# FPGA.net
KiCad netlist of a schematic drawn in Altium Designer
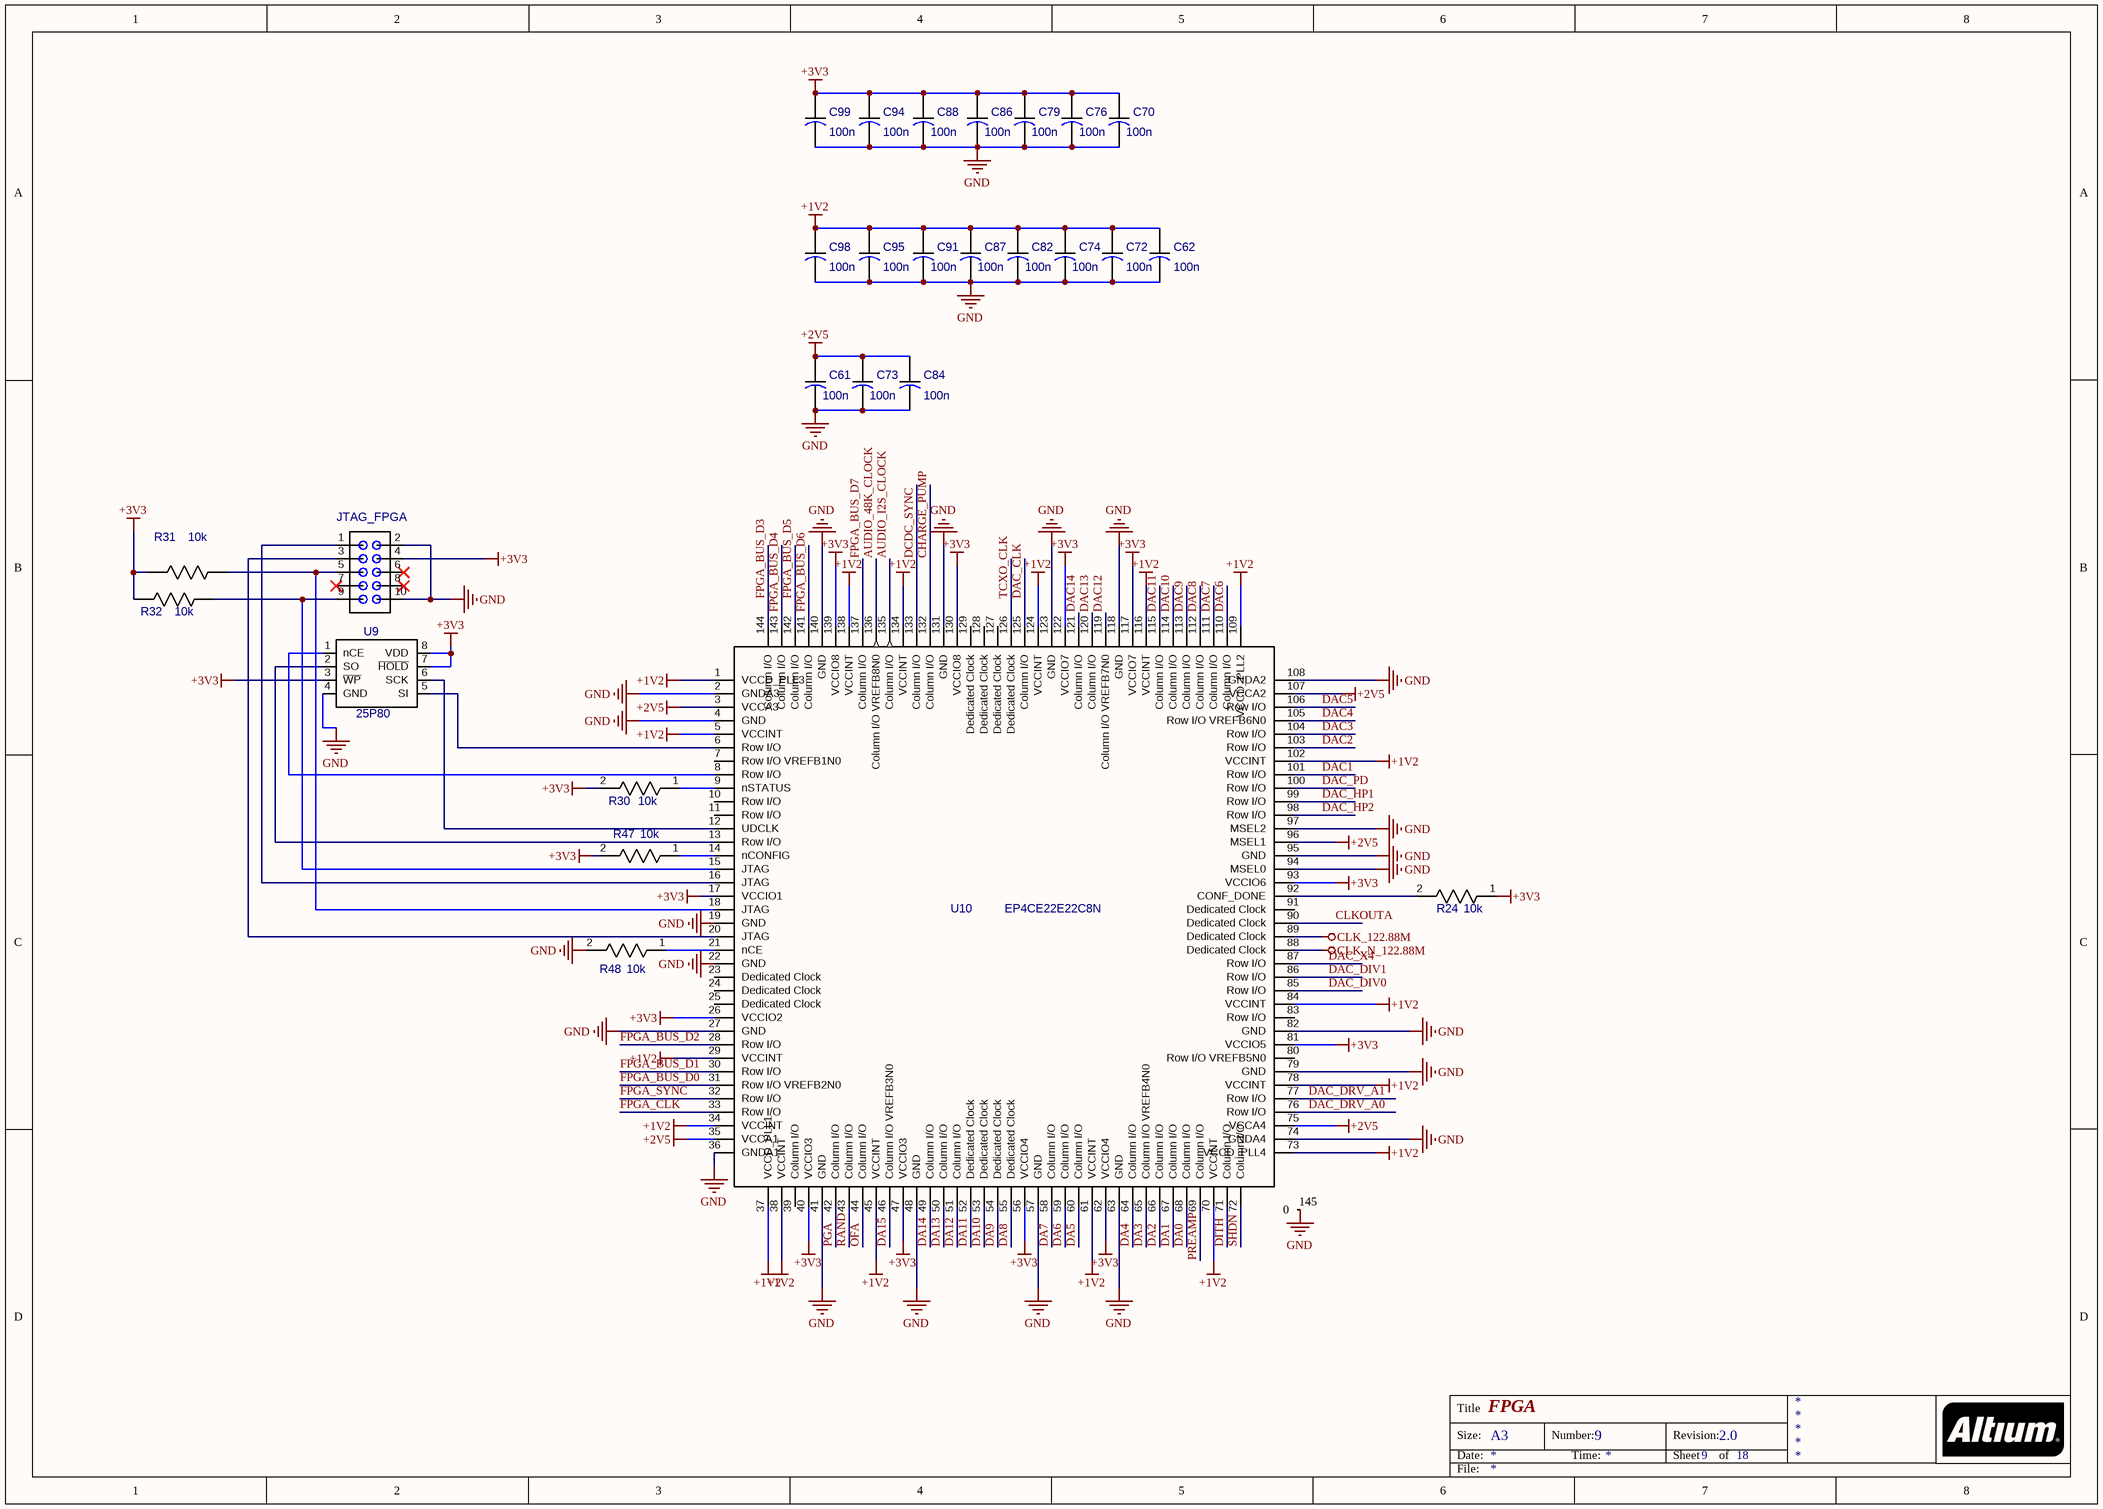
[diagram p0: FPGA.SchDoc]

(export (version "E")
  (design (tool "Eeschema 10.0.6"))
  (components
    (comp (ref "C61")
      (value "100n")
      (footprint "CAP_0805")
      (description "CAP_0805")
      (libsource (lib "*") (part "CAP_0805"))
    )
    (comp (ref "C62")
      (value "100n")
      (footprint "CAP_0805")
      (description "CAP_0805")
      (libsource (lib "*") (part "CAP_0805"))
    )
    (comp (ref "C70")
      (value "100n")
      (footprint "CAP_0805")
      (description "CAP_0805")
      (libsource (lib "*") (part "CAP_0805"))
    )
    (comp (ref "C72")
      (value "100n")
      (footprint "CAP_0805")
      (description "CAP_0805")
      (libsource (lib "*") (part "CAP_0805"))
    )
    (comp (ref "C73")
      (value "100n")
      (footprint "CAP_0805")
      (description "CAP_0805")
      (libsource (lib "*") (part "CAP_0805"))
    )
    (comp (ref "C74")
      (value "100n")
      (footprint "CAP_0805")
      (description "CAP_0805")
      (libsource (lib "*") (part "CAP_0805"))
    )
    (comp (ref "C76")
      (value "100n")
      (footprint "CAP_0805")
      (description "CAP_0805")
      (libsource (lib "*") (part "CAP_0805"))
    )
    (comp (ref "C79")
      (value "100n")
      (footprint "CAP_0805")
      (description "CAP_0805")
      (libsource (lib "*") (part "CAP_0805"))
    )
    (comp (ref "C82")
      (value "100n")
      (footprint "CAP_0805")
      (description "CAP_0805")
      (libsource (lib "*") (part "CAP_0805"))
    )
    (comp (ref "C84")
      (value "100n")
      (footprint "CAP_0805")
      (description "CAP_0805")
      (libsource (lib "*") (part "CAP_0805"))
    )
    (comp (ref "C86")
      (value "100n")
      (footprint "CAP_0805")
      (description "CAP_0805")
      (libsource (lib "*") (part "CAP_0805"))
    )
    (comp (ref "C87")
      (value "100n")
      (footprint "CAP_0805")
      (description "CAP_0805")
      (libsource (lib "*") (part "CAP_0805"))
    )
    (comp (ref "C88")
      (value "100n")
      (footprint "CAP_0805")
      (description "CAP_0805")
      (libsource (lib "*") (part "CAP_0805"))
    )
    (comp (ref "C91")
      (value "100n")
      (footprint "CAP_0805")
      (description "CAP_0805")
      (libsource (lib "*") (part "CAP_0805"))
    )
    (comp (ref "C94")
      (value "100n")
      (footprint "CAP_0805")
      (description "CAP_0805")
      (libsource (lib "*") (part "CAP_0805"))
    )
    (comp (ref "C95")
      (value "100n")
      (footprint "CAP_0805")
      (description "CAP_0805")
      (libsource (lib "*") (part "CAP_0805"))
    )
    (comp (ref "C98")
      (value "100n")
      (footprint "CAP_0805")
      (description "CAP_0805")
      (libsource (lib "*") (part "CAP_0805"))
    )
    (comp (ref "C99")
      (value "100n")
      (footprint "CAP_0805")
      (description "CAP_0805")
      (libsource (lib "*") (part "CAP_0805"))
    )
    (comp (ref "JTAG_FPGA")
      (value "~")
      (footprint "IDC10")
      (description "2*5 Pin")
      (libsource (lib "*") (part "IDC10"))
    )
    (comp (ref "R24")
      (value "10k")
      (footprint "RES_0805")
      (description "RES_0805")
      (libsource (lib "") (part "RES_0805_1"))
    )
    (comp (ref "R30")
      (value "10k")
      (footprint "RES_0805")
      (description "RES_0805")
      (libsource (lib "") (part "RES_0805_1"))
    )
    (comp (ref "R31")
      (value "10k")
      (footprint "RES_0805")
      (description "RES_0805")
      (libsource (lib "*") (part "RES_0805"))
    )
    (comp (ref "R32")
      (value "10k")
      (footprint "RES_0805")
      (description "RES_0805")
      (libsource (lib "*") (part "RES_0805"))
    )
    (comp (ref "R47")
      (value "10k")
      (footprint "RES_0805")
      (description "RES_0805")
      (libsource (lib "") (part "RES_0805_1"))
    )
    (comp (ref "R48")
      (value "10k")
      (footprint "RES_0805")
      (description "RES_0805")
      (libsource (lib "") (part "RES_0805_1"))
    )
    (comp (ref "U9") (value "25P80") (footprint "25P80") (libsource (lib "*") (part "25P80")))
    (comp (ref "U10")
      (value "EP4CE22E22C8N")
      (footprint "QFP144-20-2222A")
      (libsource (lib "*") (part "EP4CE22E22C8N"))
    )
  )
  (nets
    (net (code "1") (name "+1V2") (class "Default")
      (node (ref "C62") (pin "1") (pinfunction "1_1") (pintype "passive"))
      (node (ref "C72") (pin "1") (pinfunction "1_1") (pintype "passive"))
      (node (ref "C74") (pin "1") (pinfunction "1_1") (pintype "passive"))
      (node (ref "C82") (pin "1") (pinfunction "1_1") (pintype "passive"))
      (node (ref "C87") (pin "1") (pinfunction "1_1") (pintype "passive"))
      (node (ref "C91") (pin "1") (pinfunction "1_1") (pintype "passive"))
      (node (ref "C95") (pin "1") (pinfunction "1_1") (pintype "passive"))
      (node (ref "C98") (pin "1") (pinfunction "1_1") (pintype "passive"))
      (node (ref "U10") (pin "1") (pinfunction "VCCD_PLL3_1") (pintype "passive"))
      (node (ref "U10") (pin "102") (pinfunction "VCCINT_102") (pintype "passive"))
      (node (ref "U10") (pin "109") (pinfunction "VCCD_PLL2_109") (pintype "passive"))
      (node (ref "U10") (pin "116") (pinfunction "VCCINT_116") (pintype "passive"))
      (node (ref "U10") (pin "124") (pinfunction "VCCINT_124") (pintype "passive"))
      (node (ref "U10") (pin "134") (pinfunction "VCCINT_134") (pintype "passive"))
      (node (ref "U10") (pin "138") (pinfunction "VCCINT_138") (pintype "passive"))
      (node (ref "U10") (pin "29") (pinfunction "VCCINT_29") (pintype "passive"))
      (node (ref "U10") (pin "34") (pinfunction "VCCINT_34") (pintype "passive"))
      (node (ref "U10") (pin "37") (pinfunction "VCCD_PLL1_37") (pintype "passive"))
      (node (ref "U10") (pin "38") (pinfunction "VCCINT_38") (pintype "passive"))
      (node (ref "U10") (pin "45") (pinfunction "VCCINT_45") (pintype "passive"))
      (node (ref "U10") (pin "5") (pinfunction "VCCINT_5") (pintype "passive"))
      (node (ref "U10") (pin "61") (pinfunction "VCCINT_61") (pintype "passive"))
      (node (ref "U10") (pin "70") (pinfunction "VCCINT_70") (pintype "passive"))
      (node (ref "U10") (pin "73") (pinfunction "VCCD_PLL4_73") (pintype "passive"))
      (node (ref "U10") (pin "78") (pinfunction "VCCINT_78") (pintype "passive"))
      (node (ref "U10") (pin "84") (pinfunction "VCCINT_84") (pintype "passive"))
    )
    (net (code "2") (name "+2V5") (class "Default")
      (node (ref "C61") (pin "1") (pinfunction "1_1") (pintype "passive"))
      (node (ref "C73") (pin "1") (pinfunction "1_1") (pintype "passive"))
      (node (ref "C84") (pin "1") (pinfunction "1_1") (pintype "passive"))
      (node (ref "U10") (pin "107") (pinfunction "VCCA2_107") (pintype "passive"))
      (node (ref "U10") (pin "3") (pinfunction "VCCA3_3") (pintype "passive"))
      (node (ref "U10") (pin "35") (pinfunction "VCCA1_35") (pintype "passive"))
      (node (ref "U10") (pin "75") (pinfunction "VCCA4_75") (pintype "passive"))
      (node (ref "U10") (pin "96") (pinfunction "MSEL1_96") (pintype "passive"))
    )
    (net (code "3") (name "+3V3") (class "Default")
      (node (ref "C70") (pin "1") (pinfunction "1_1") (pintype "passive"))
      (node (ref "C76") (pin "1") (pinfunction "1_1") (pintype "passive"))
      (node (ref "C79") (pin "1") (pinfunction "1_1") (pintype "passive"))
      (node (ref "C86") (pin "1") (pinfunction "1_1") (pintype "passive"))
      (node (ref "C88") (pin "1") (pinfunction "1_1") (pintype "passive"))
      (node (ref "C94") (pin "1") (pinfunction "1_1") (pintype "passive"))
      (node (ref "C99") (pin "1") (pinfunction "1_1") (pintype "passive"))
      (node (ref "JTAG_FPGA") (pin "4") (pinfunction "4_4") (pintype "passive"))
      (node (ref "R24") (pin "1") (pinfunction "1_1") (pintype "passive"))
      (node (ref "R30") (pin "2") (pinfunction "2_2") (pintype "passive"))
      (node (ref "R31") (pin "2") (pinfunction "2_2") (pintype "passive"))
      (node (ref "R32") (pin "2") (pinfunction "2_2") (pintype "passive"))
      (node (ref "R47") (pin "2") (pinfunction "2_2") (pintype "passive"))
      (node (ref "U10") (pin "117") (pinfunction "VCCIO7_117") (pintype "passive"))
      (node (ref "U10") (pin "122") (pinfunction "VCCIO7_122") (pintype "passive"))
      (node (ref "U10") (pin "130") (pinfunction "VCCIO8_130") (pintype "passive"))
      (node (ref "U10") (pin "139") (pinfunction "VCCIO8_139") (pintype "passive"))
      (node (ref "U10") (pin "17") (pinfunction "VCCIO1_17") (pintype "passive"))
      (node (ref "U10") (pin "26") (pinfunction "VCCIO2_26") (pintype "passive"))
      (node (ref "U10") (pin "40") (pinfunction "VCCIO3_40") (pintype "passive"))
      (node (ref "U10") (pin "47") (pinfunction "VCCIO3_47") (pintype "passive"))
      (node (ref "U10") (pin "56") (pinfunction "VCCIO4_56") (pintype "passive"))
      (node (ref "U10") (pin "62") (pinfunction "VCCIO4_62") (pintype "passive"))
      (node (ref "U10") (pin "81") (pinfunction "VCCIO5_81") (pintype "passive"))
      (node (ref "U10") (pin "93") (pinfunction "VCCIO6_93") (pintype "passive"))
      (node (ref "U9") (pin "3") (pinfunction "~{WP}_3") (pintype "passive"))
      (node (ref "U9") (pin "7") (pinfunction "~{HOLD}_7") (pintype "passive"))
      (node (ref "U9") (pin "8") (pinfunction "VDD_8") (pintype "passive"))
    )
    (net (code "4") (name "/AUDIO_48K_CLOCK") (class "Default")
      (node (ref "U10") (pin "136") (pinfunction "Column_I/O_VREFB8N0_136") (pintype "output"))
    )
    (net (code "5") (name "/AUDIO_I2S_CLOCK") (class "Default")
      (node (ref "U10") (pin "135") (pinfunction "Column_I/O_135") (pintype "output"))
    )
    (net (code "6") (name "/CHARGE_PUMP") (class "Default")
      (node (ref "U10") (pin "132") (pinfunction "Column_I/O_132") (pintype "passive"))
    )
    (net (code "7") (name "/CLKOUTA") (class "Default")
      (node (ref "U10") (pin "90") (pinfunction "Dedicated_Clock_90") (pintype "passive"))
    )
    (net (code "8") (name "/DA0") (class "Default")
      (node (ref "U10") (pin "68") (pinfunction "Column_I/O_68") (pintype "passive"))
    )
    (net (code "9") (name "/DA1") (class "Default")
      (node (ref "U10") (pin "67") (pinfunction "Column_I/O_67") (pintype "passive"))
    )
    (net (code "10") (name "/DA2") (class "Default")
      (node (ref "U10") (pin "66") (pinfunction "Column_I/O_66") (pintype "passive"))
    )
    (net (code "11") (name "/DA3") (class "Default")
      (node (ref "U10") (pin "65") (pinfunction "Column_I/O_VREFB4N0_65") (pintype "passive"))
    )
    (net (code "12") (name "/DA4") (class "Default")
      (node (ref "U10") (pin "64") (pinfunction "Column_I/O_64") (pintype "passive"))
    )
    (net (code "13") (name "/DA5") (class "Default")
      (node (ref "U10") (pin "60") (pinfunction "Column_I/O_60") (pintype "passive"))
    )
    (net (code "14") (name "/DA6") (class "Default")
      (node (ref "U10") (pin "59") (pinfunction "Column_I/O_59") (pintype "passive"))
    )
    (net (code "15") (name "/DA7") (class "Default")
      (node (ref "U10") (pin "58") (pinfunction "Column_I/O_58") (pintype "passive"))
    )
    (net (code "16") (name "/DA8") (class "Default")
      (node (ref "U10") (pin "55") (pinfunction "Dedicated_Clock_55") (pintype "passive"))
    )
    (net (code "17") (name "/DA9") (class "Default")
      (node (ref "U10") (pin "54") (pinfunction "Dedicated_Clock_54") (pintype "passive"))
    )
    (net (code "18") (name "/DA10") (class "Default")
      (node (ref "U10") (pin "53") (pinfunction "Dedicated_Clock_53") (pintype "passive"))
    )
    (net (code "19") (name "/DA11") (class "Default")
      (node (ref "U10") (pin "52") (pinfunction "Dedicated_Clock_52") (pintype "passive"))
    )
    (net (code "20") (name "/DA12") (class "Default")
      (node (ref "U10") (pin "51") (pinfunction "Column_I/O_51") (pintype "passive"))
    )
    (net (code "21") (name "/DA13") (class "Default")
      (node (ref "U10") (pin "50") (pinfunction "Column_I/O_50") (pintype "passive"))
    )
    (net (code "22") (name "/DA14") (class "Default")
      (node (ref "U10") (pin "49") (pinfunction "Column_I/O_49") (pintype "passive"))
    )
    (net (code "23") (name "/DA15") (class "Default")
      (node (ref "U10") (pin "46") (pinfunction "Column_I/O_VREFB3N0_46") (pintype "passive"))
    )
    (net (code "24") (name "/DAC1") (class "Default")
      (node (ref "U10") (pin "101") (pinfunction "Row_I/O_101") (pintype "passive"))
    )
    (net (code "25") (name "/DAC2") (class "Default")
      (node (ref "U10") (pin "103") (pinfunction "Row_I/O_103") (pintype "passive"))
    )
    (net (code "26") (name "/DAC3") (class "Default")
      (node (ref "U10") (pin "104") (pinfunction "Row_I/O_104") (pintype "passive"))
    )
    (net (code "27") (name "/DAC4") (class "Default")
      (node (ref "U10") (pin "105") (pinfunction "Row_I/O_VREFB6N0_105") (pintype "passive"))
    )
    (net (code "28") (name "/DAC5") (class "Default")
      (node (ref "U10") (pin "106") (pinfunction "Row_I/O_106") (pintype "passive"))
    )
    (net (code "29") (name "/DAC6") (class "Default")
      (node (ref "U10") (pin "110") (pinfunction "Column_I/O_110") (pintype "passive"))
    )
    (net (code "30") (name "/DAC7") (class "Default")
      (node (ref "U10") (pin "111") (pinfunction "Column_I/O_111") (pintype "passive"))
    )
    (net (code "31") (name "/DAC8") (class "Default")
      (node (ref "U10") (pin "112") (pinfunction "Column_I/O_112") (pintype "passive"))
    )
    (net (code "32") (name "/DAC9") (class "Default")
      (node (ref "U10") (pin "113") (pinfunction "Column_I/O_113") (pintype "passive"))
    )
    (net (code "33") (name "/DAC10") (class "Default")
      (node (ref "U10") (pin "114") (pinfunction "Column_I/O_114") (pintype "passive"))
    )
    (net (code "34") (name "/DAC11") (class "Default")
      (node (ref "U10") (pin "115") (pinfunction "Column_I/O_115") (pintype "passive"))
    )
    (net (code "35") (name "/DAC12") (class "Default")
      (node (ref "U10") (pin "119") (pinfunction "Column_I/O_VREFB7N0_119") (pintype "passive"))
    )
    (net (code "36") (name "/DAC13") (class "Default")
      (node (ref "U10") (pin "120") (pinfunction "Column_I/O_120") (pintype "passive"))
    )
    (net (code "37") (name "/DAC14") (class "Default")
      (node (ref "U10") (pin "121") (pinfunction "Column_I/O_121") (pintype "passive"))
    )
    (net (code "38") (name "/DAC_CLK") (class "Default")
      (node (ref "U10") (pin "125") (pinfunction "Column_I/O_125") (pintype "passive"))
    )
    (net (code "39") (name "/DAC_DIV0") (class "Default")
      (node (ref "U10") (pin "85") (pinfunction "Row_I/O_85") (pintype "passive"))
    )
    (net (code "40") (name "/DAC_DIV1") (class "Default")
      (node (ref "U10") (pin "86") (pinfunction "Row_I/O_86") (pintype "passive"))
    )
    (net (code "41") (name "/DAC_DRV_A0") (class "Default")
      (node (ref "U10") (pin "76") (pinfunction "Row_I/O_76") (pintype "passive"))
    )
    (net (code "42") (name "/DAC_DRV_A1") (class "Default")
      (node (ref "U10") (pin "77") (pinfunction "Row_I/O_77") (pintype "passive"))
    )
    (net (code "43") (name "/DAC_HP1") (class "Default")
      (node (ref "U10") (pin "99") (pinfunction "Row_I/O_99") (pintype "passive"))
    )
    (net (code "44") (name "/DAC_HP2") (class "Default")
      (node (ref "U10") (pin "98") (pinfunction "Row_I/O_98") (pintype "passive"))
    )
    (net (code "45") (name "/DAC_PD") (class "Default")
      (node (ref "U10") (pin "100") (pinfunction "Row_I/O_100") (pintype "passive"))
    )
    (net (code "46") (name "/DAC_X4") (class "Default")
      (node (ref "U10") (pin "87") (pinfunction "Row_I/O_87") (pintype "passive"))
    )
    (net (code "47") (name "/DCDC_SYNC") (class "Default")
      (node (ref "U10") (pin "133") (pinfunction "Column_I/O_133") (pintype "passive"))
    )
    (net (code "48") (name "/DITH") (class "Default")
      (node (ref "U10") (pin "71") (pinfunction "Column_I/O_71") (pintype "passive"))
    )
    (net (code "49") (name "/FPGA_BUS_D0") (class "Default")
      (node (ref "U10") (pin "31") (pinfunction "Row_I/O_VREFB2N0_31") (pintype "passive"))
    )
    (net (code "50") (name "/FPGA_BUS_D1") (class "Default")
      (node (ref "U10") (pin "30") (pinfunction "Row_I/O_30") (pintype "passive"))
    )
    (net (code "51") (name "/FPGA_BUS_D2") (class "Default")
      (node (ref "U10") (pin "28") (pinfunction "Row_I/O_28") (pintype "passive"))
    )
    (net (code "52") (name "/FPGA_BUS_D3") (class "Default")
      (node (ref "U10") (pin "144") (pinfunction "Column_I/O_144") (pintype "passive"))
    )
    (net (code "53") (name "/FPGA_BUS_D4") (class "Default")
      (node (ref "U10") (pin "143") (pinfunction "Column_I/O_143") (pintype "passive"))
    )
    (net (code "54") (name "/FPGA_BUS_D5") (class "Default")
      (node (ref "U10") (pin "142") (pinfunction "Column_I/O_142") (pintype "passive"))
    )
    (net (code "55") (name "/FPGA_BUS_D6") (class "Default")
      (node (ref "U10") (pin "141") (pinfunction "Column_I/O_141") (pintype "passive"))
    )
    (net (code "56") (name "/FPGA_BUS_D7") (class "Default")
      (node (ref "U10") (pin "137") (pinfunction "Column_I/O_137") (pintype "passive"))
    )
    (net (code "57") (name "/FPGA_CLK") (class "Default")
      (node (ref "U10") (pin "33") (pinfunction "Row_I/O_33") (pintype "passive"))
    )
    (net (code "58") (name "/FPGA_SYNC") (class "Default")
      (node (ref "U10") (pin "32") (pinfunction "Row_I/O_32") (pintype "passive"))
    )
    (net (code "59") (name "/OFA") (class "Default")
      (node (ref "U10") (pin "44") (pinfunction "Column_I/O_44") (pintype "passive"))
    )
    (net (code "60") (name "/PGA") (class "Default")
      (node (ref "U10") (pin "42") (pinfunction "Column_I/O_42") (pintype "passive"))
    )
    (net (code "61") (name "/PREAMP") (class "Default")
      (node (ref "U10") (pin "69") (pinfunction "Column_I/O_69") (pintype "passive"))
    )
    (net (code "62") (name "/RAND") (class "Default")
      (node (ref "U10") (pin "43") (pinfunction "Column_I/O_43") (pintype "passive"))
    )
    (net (code "63") (name "/SHDN") (class "Default")
      (node (ref "U10") (pin "72") (pinfunction "Column_I/O_72") (pintype "passive"))
    )
    (net (code "64") (name "/TCXO_CLK") (class "Default")
      (node (ref "U10") (pin "126") (pinfunction "Dedicated_Clock_126") (pintype "passive"))
    )
    (net (code "65") (name "CLK_122.88M") (class "Default")
      (node (ref "U10") (pin "89") (pinfunction "Dedicated_Clock_89") (pintype "passive"))
    )
    (net (code "66") (name "CLK_N_122.88M") (class "Default")
      (node (ref "U10") (pin "88") (pinfunction "Dedicated_Clock_88") (pintype "passive"))
    )
    (net (code "67") (name "GND") (class "Default")
      (node (ref "C61") (pin "2") (pinfunction "2_2") (pintype "passive"))
      (node (ref "C62") (pin "2") (pinfunction "2_2") (pintype "passive"))
      (node (ref "C70") (pin "2") (pinfunction "2_2") (pintype "passive"))
      (node (ref "C72") (pin "2") (pinfunction "2_2") (pintype "passive"))
      (node (ref "C73") (pin "2") (pinfunction "2_2") (pintype "passive"))
      (node (ref "C74") (pin "2") (pinfunction "2_2") (pintype "passive"))
      (node (ref "C76") (pin "2") (pinfunction "2_2") (pintype "passive"))
      (node (ref "C79") (pin "2") (pinfunction "2_2") (pintype "passive"))
      (node (ref "C82") (pin "2") (pinfunction "2_2") (pintype "passive"))
      (node (ref "C84") (pin "2") (pinfunction "2_2") (pintype "passive"))
      (node (ref "C86") (pin "2") (pinfunction "2_2") (pintype "passive"))
      (node (ref "C87") (pin "2") (pinfunction "2_2") (pintype "passive"))
      (node (ref "C88") (pin "2") (pinfunction "2_2") (pintype "passive"))
      (node (ref "C91") (pin "2") (pinfunction "2_2") (pintype "passive"))
      (node (ref "C94") (pin "2") (pinfunction "2_2") (pintype "passive"))
      (node (ref "C95") (pin "2") (pinfunction "2_2") (pintype "passive"))
      (node (ref "C98") (pin "2") (pinfunction "2_2") (pintype "passive"))
      (node (ref "C99") (pin "2") (pinfunction "2_2") (pintype "passive"))
      (node (ref "JTAG_FPGA") (pin "10") (pinfunction "10_10") (pintype "passive"))
      (node (ref "JTAG_FPGA") (pin "2") (pinfunction "2_2") (pintype "passive"))
      (node (ref "R48") (pin "2") (pinfunction "2_2") (pintype "passive"))
      (node (ref "U10") (pin "108") (pinfunction "GNDA2_108") (pintype "passive"))
      (node (ref "U10") (pin "118") (pinfunction "GND_118") (pintype "passive"))
      (node (ref "U10") (pin "123") (pinfunction "GND_123") (pintype "passive"))
      (node (ref "U10") (pin "131") (pinfunction "GND_131") (pintype "passive"))
      (node (ref "U10") (pin "140") (pinfunction "GND_140") (pintype "passive"))
      (node (ref "U10") (pin "145") (pinfunction "0_145") (pintype "passive"))
      (node (ref "U10") (pin "19") (pinfunction "GND_19") (pintype "passive"))
      (node (ref "U10") (pin "2") (pinfunction "GNDA3_2") (pintype "passive"))
      (node (ref "U10") (pin "22") (pinfunction "GND_22") (pintype "passive"))
      (node (ref "U10") (pin "27") (pinfunction "GND_27") (pintype "passive"))
      (node (ref "U10") (pin "36") (pinfunction "GNDA1_36") (pintype "passive"))
      (node (ref "U10") (pin "4") (pinfunction "GND_4") (pintype "passive"))
      (node (ref "U10") (pin "41") (pinfunction "GND_41") (pintype "passive"))
      (node (ref "U10") (pin "48") (pinfunction "GND_48") (pintype "passive"))
      (node (ref "U10") (pin "57") (pinfunction "GND_57") (pintype "passive"))
      (node (ref "U10") (pin "63") (pinfunction "GND_63") (pintype "passive"))
      (node (ref "U10") (pin "74") (pinfunction "GNDA4_74") (pintype "passive"))
      (node (ref "U10") (pin "79") (pinfunction "GND_79") (pintype "passive"))
      (node (ref "U10") (pin "82") (pinfunction "GND_82") (pintype "passive"))
      (node (ref "U10") (pin "94") (pinfunction "MSEL0_94") (pintype "passive"))
      (node (ref "U10") (pin "95") (pinfunction "GND_95") (pintype "passive"))
      (node (ref "U10") (pin "97") (pinfunction "MSEL2_97") (pintype "passive"))
      (node (ref "U9") (pin "4") (pinfunction "GND_4") (pintype "passive"))
    )
    (net (code "68") (name "Net-(JTAG_FPGA-Pad1)") (class "Default")
      (node (ref "JTAG_FPGA") (pin "1") (pinfunction "1_1") (pintype "passive"))
      (node (ref "U10") (pin "16") (pinfunction "JTAG_16") (pintype "passive"))
    )
    (net (code "69") (name "Net-(JTAG_FPGA-Pad3)") (class "Default")
      (node (ref "JTAG_FPGA") (pin "3") (pinfunction "3_3") (pintype "passive"))
      (node (ref "U10") (pin "20") (pinfunction "JTAG_20") (pintype "passive"))
    )
    (net (code "70") (name "Net-(JTAG_FPGA-Pad5)") (class "Default")
      (node (ref "JTAG_FPGA") (pin "5") (pinfunction "5_5") (pintype "passive"))
      (node (ref "R31") (pin "1") (pinfunction "1_1") (pintype "passive"))
      (node (ref "U10") (pin "18") (pinfunction "JTAG_18") (pintype "passive"))
    )
    (net (code "71") (name "Net-(JTAG_FPGA-Pad9)") (class "Default")
      (node (ref "JTAG_FPGA") (pin "9") (pinfunction "9_9") (pintype "passive"))
      (node (ref "R32") (pin "1") (pinfunction "1_1") (pintype "passive"))
      (node (ref "U10") (pin "15") (pinfunction "JTAG_15") (pintype "passive"))
    )
    (net (code "72") (name "Net-(U9-SI)") (class "Default")
      (node (ref "U10") (pin "6") (pinfunction "Row_I/O_6") (pintype "passive"))
      (node (ref "U9") (pin "5") (pinfunction "SI_5") (pintype "passive"))
    )
    (net (code "73") (name "Net-(U9-SO)") (class "Default")
      (node (ref "U10") (pin "13") (pinfunction "Row_I/O_13") (pintype "passive"))
      (node (ref "U9") (pin "2") (pinfunction "SO_2") (pintype "passive"))
    )
    (net (code "74") (name "Net-(U9-nCE)") (class "Default")
      (node (ref "U10") (pin "8") (pinfunction "Row_I/O_8") (pintype "passive"))
      (node (ref "U9") (pin "1") (pinfunction "nCE_1") (pintype "passive"))
    )
    (net (code "75") (name "Net-(U10-CONF_DONE)") (class "Default")
      (node (ref "R24") (pin "2") (pinfunction "2_2") (pintype "passive"))
      (node (ref "U10") (pin "92") (pinfunction "CONF_DONE_92") (pintype "passive"))
    )
    (net (code "76") (name "Net-(U10-UDCLK)") (class "Default")
      (node (ref "U10") (pin "12") (pinfunction "UDCLK_12") (pintype "passive"))
      (node (ref "U9") (pin "6") (pinfunction "SCK_6") (pintype "passive"))
    )
    (net (code "77") (name "Net-(U10-nCE)") (class "Default")
      (node (ref "R48") (pin "1") (pinfunction "1_1") (pintype "passive"))
      (node (ref "U10") (pin "21") (pinfunction "nCE_21") (pintype "passive"))
    )
    (net (code "78") (name "Net-(U10-nCONFIG)") (class "Default")
      (node (ref "R47") (pin "1") (pinfunction "1_1") (pintype "passive"))
      (node (ref "U10") (pin "14") (pinfunction "nCONFIG_14") (pintype "passive"))
    )
    (net (code "79") (name "Net-(U10-nSTATUS)") (class "Default")
      (node (ref "R30") (pin "1") (pinfunction "1_1") (pintype "passive"))
      (node (ref "U10") (pin "9") (pinfunction "nSTATUS_9") (pintype "passive"))
    )
    (net (code "80") (name "unconnected-(JTAG_FPGA-Pad6)") (class "Default")
      (node (ref "JTAG_FPGA") (pin "6") (pinfunction "6_6") (pintype "passive+no_connect"))
    )
    (net (code "81") (name "unconnected-(JTAG_FPGA-Pad7)") (class "Default")
      (node (ref "JTAG_FPGA") (pin "7") (pinfunction "7_7") (pintype "passive+no_connect"))
    )
    (net (code "82") (name "unconnected-(JTAG_FPGA-Pad8)") (class "Default")
      (node (ref "JTAG_FPGA") (pin "8") (pinfunction "8_8") (pintype "passive+no_connect"))
    )
    (net (code "83") (name "unconnected-(U10-Column_I{slash}O-Pad39)") (class "Default")
      (node (ref "U10") (pin "39") (pinfunction "Column_I/O_39") (pintype "passive"))
    )
    (net (code "84") (name "unconnected-(U10-Dedicated_Clock-Pad23)") (class "Default")
      (node (ref "U10") (pin "23") (pinfunction "Dedicated_Clock_23") (pintype "passive"))
    )
    (net (code "85") (name "unconnected-(U10-Dedicated_Clock-Pad24)") (class "Default")
      (node (ref "U10") (pin "24") (pinfunction "Dedicated_Clock_24") (pintype "passive"))
    )
    (net (code "86") (name "unconnected-(U10-Dedicated_Clock-Pad25)") (class "Default")
      (node (ref "U10") (pin "25") (pinfunction "Dedicated_Clock_25") (pintype "passive"))
    )
    (net (code "87") (name "unconnected-(U10-Dedicated_Clock-Pad91)") (class "Default")
      (node (ref "U10") (pin "91") (pinfunction "Dedicated_Clock_91") (pintype "passive"))
    )
    (net (code "88") (name "unconnected-(U10-Dedicated_Clock-Pad127)") (class "Default")
      (node (ref "U10") (pin "127") (pinfunction "Dedicated_Clock_127") (pintype "passive"))
    )
    (net (code "89") (name "unconnected-(U10-Dedicated_Clock-Pad128)") (class "Default")
      (node (ref "U10") (pin "128") (pinfunction "Dedicated_Clock_128") (pintype "passive"))
    )
    (net (code "90") (name "unconnected-(U10-Dedicated_Clock-Pad129)") (class "Default")
      (node (ref "U10") (pin "129") (pinfunction "Dedicated_Clock_129") (pintype "passive"))
    )
    (net (code "91") (name "unconnected-(U10-Row_I{slash}O-Pad10)") (class "Default")
      (node (ref "U10") (pin "10") (pinfunction "Row_I/O_10") (pintype "passive"))
    )
    (net (code "92") (name "unconnected-(U10-Row_I{slash}O-Pad11)") (class "Default")
      (node (ref "U10") (pin "11") (pinfunction "Row_I/O_11") (pintype "passive"))
    )
    (net (code "93") (name "unconnected-(U10-Row_I{slash}O-Pad83)") (class "Default")
      (node (ref "U10") (pin "83") (pinfunction "Row_I/O_83") (pintype "passive"))
    )
    (net (code "94") (name "unconnected-(U10-Row_I{slash}O_VREFB1N0-Pad7)") (class "Default")
      (node (ref "U10") (pin "7") (pinfunction "Row_I/O_VREFB1N0_7") (pintype "passive"))
    )
    (net (code "95") (name "unconnected-(U10-Row_I{slash}O_VREFB5N0-Pad80)") (class "Default")
      (node (ref "U10") (pin "80") (pinfunction "Row_I/O_VREFB5N0_80") (pintype "passive"))
    )
  )
)
